# Power.net
KiCad netlist of a schematic drawn in Altium Designer
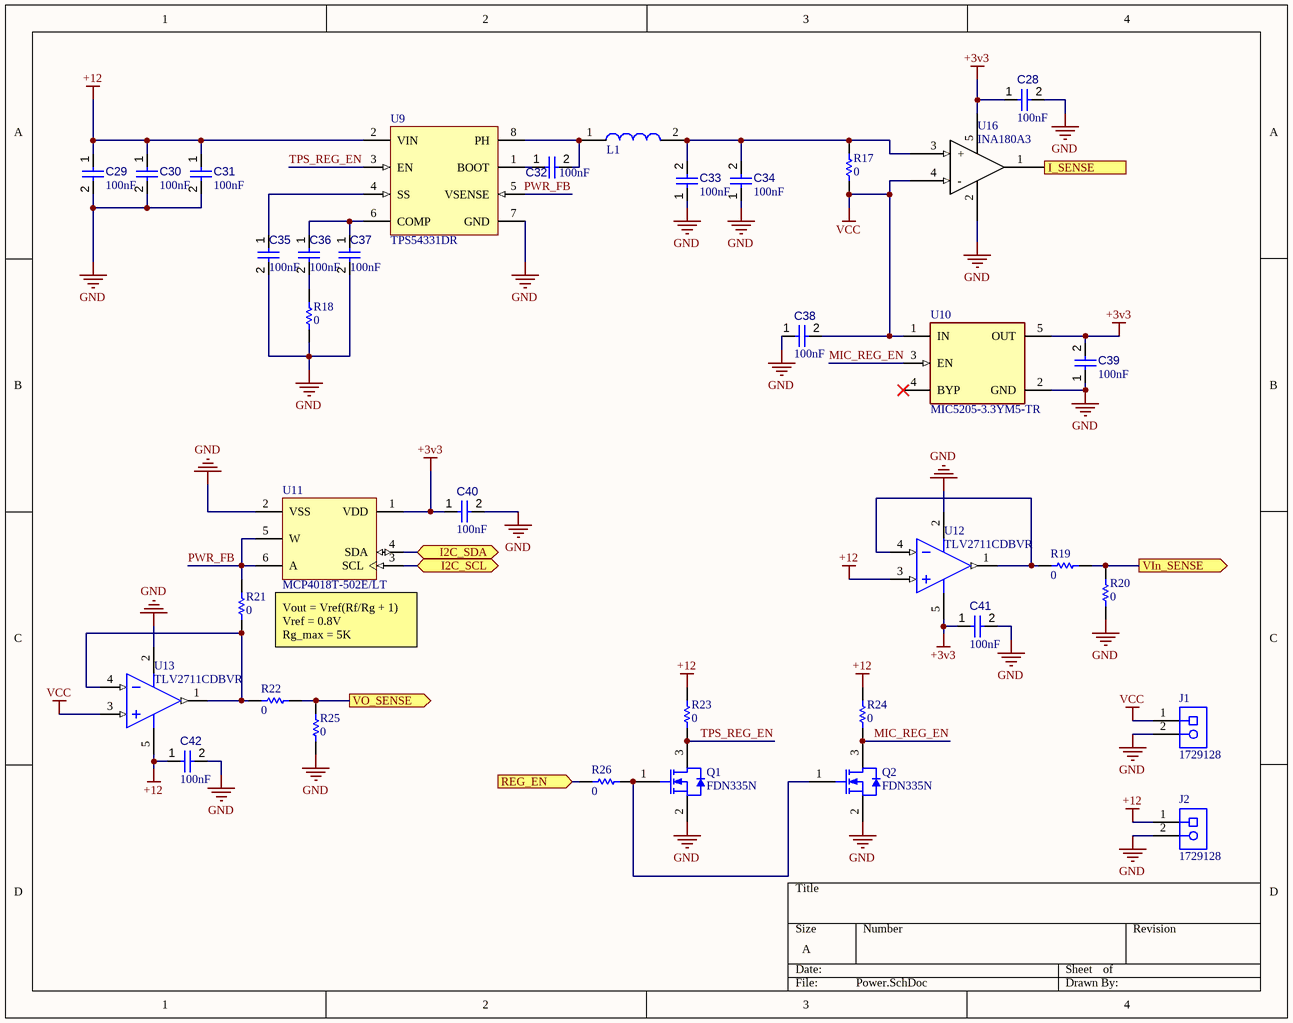
[diagram p0: Power.SchDoc]

(export (version "E")
  (design (tool "Eeschema 10.0.6"))
  (components
    (comp (ref "C28")
      (value "100nF")
      (footprint "CAPC2013X95X50ML10T25")
      (description "Chip Capacitor, 100 nF, +/- 10%, 50 V, 0805 (2012 Metric)")
      (fields (field (name "TOLERANCE") "10%") (field (name "Comment") "Capacitor 100 nF +/-10% 50 V 0805"))
      (libsource (lib "Aditya Sehgal") (part "CAP-NP-2"))
    )
    (comp (ref "C29")
      (value "100nF")
      (footprint "CAPC2013X95X50ML10T25")
      (description "Chip Capacitor, 100 nF, +/- 10%, 50 V, 0805 (2012 Metric)")
      (fields (field (name "TOLERANCE") "10%") (field (name "Comment") "Capacitor 100 nF +/-10% 50 V 0805"))
      (libsource (lib "Aditya Sehgal") (part "CAP-NP-2"))
    )
    (comp (ref "C30")
      (value "100nF")
      (footprint "CAPC2013X95X50ML10T25")
      (description "Chip Capacitor, 100 nF, +/- 10%, 50 V, 0805 (2012 Metric)")
      (fields (field (name "TOLERANCE") "10%") (field (name "Comment") "Capacitor 100 nF +/-10% 50 V 0805"))
      (libsource (lib "Aditya Sehgal") (part "CAP-NP-2"))
    )
    (comp (ref "C31")
      (value "100nF")
      (footprint "CAPC2013X95X50ML10T25")
      (description "Chip Capacitor, 100 nF, +/- 10%, 50 V, 0805 (2012 Metric)")
      (fields (field (name "TOLERANCE") "10%") (field (name "Comment") "Capacitor 100 nF +/-10% 50 V 0805"))
      (libsource (lib "Aditya Sehgal") (part "CAP-NP-2"))
    )
    (comp (ref "C32")
      (value "100nF")
      (footprint "CAPC2013X95X50ML10T25")
      (description "Chip Capacitor, 100 nF, +/- 10%, 50 V, 0805 (2012 Metric)")
      (fields (field (name "TOLERANCE") "10%") (field (name "Comment") "Capacitor 100 nF +/-10% 50 V 0805"))
      (libsource (lib "Aditya Sehgal") (part "CAP-NP-2"))
    )
    (comp (ref "C33")
      (value "100nF")
      (footprint "CAPC2013X95X50ML10T25")
      (description "Chip Capacitor, 100 nF, +/- 10%, 50 V, 0805 (2012 Metric)")
      (fields (field (name "TOLERANCE") "10%") (field (name "Comment") "Capacitor 100 nF +/-10% 50 V 0805"))
      (libsource (lib "Aditya Sehgal") (part "CAP-NP-2"))
    )
    (comp (ref "C34")
      (value "100nF")
      (footprint "CAPC2013X95X50ML10T25")
      (description "Chip Capacitor, 100 nF, +/- 10%, 50 V, 0805 (2012 Metric)")
      (fields (field (name "TOLERANCE") "10%") (field (name "Comment") "Capacitor 100 nF +/-10% 50 V 0805"))
      (libsource (lib "Aditya Sehgal") (part "CAP-NP-2"))
    )
    (comp (ref "C35")
      (value "100nF")
      (footprint "CAPC2013X95X50ML10T25")
      (description "Chip Capacitor, 100 nF, +/- 10%, 50 V, 0805 (2012 Metric)")
      (fields (field (name "TOLERANCE") "10%") (field (name "Comment") "Capacitor 100 nF +/-10% 50 V 0805"))
      (libsource (lib "Aditya Sehgal") (part "CAP-NP-2"))
    )
    (comp (ref "C36")
      (value "100nF")
      (footprint "CAPC2013X95X50ML10T25")
      (description "Chip Capacitor, 100 nF, +/- 10%, 50 V, 0805 (2012 Metric)")
      (fields (field (name "TOLERANCE") "10%") (field (name "Comment") "Capacitor 100 nF +/-10% 50 V 0805"))
      (libsource (lib "Aditya Sehgal") (part "CAP-NP-2"))
    )
    (comp (ref "C37")
      (value "100nF")
      (footprint "CAPC2013X95X50ML10T25")
      (description "Chip Capacitor, 100 nF, +/- 10%, 50 V, 0805 (2012 Metric)")
      (fields (field (name "TOLERANCE") "10%") (field (name "Comment") "Capacitor 100 nF +/-10% 50 V 0805"))
      (libsource (lib "Aditya Sehgal") (part "CAP-NP-2"))
    )
    (comp (ref "C38")
      (value "100nF")
      (footprint "CAPC2013X95X50ML10T25")
      (description "Chip Capacitor, 100 nF, +/- 10%, 50 V, 0805 (2012 Metric)")
      (fields (field (name "TOLERANCE") "10%") (field (name "Comment") "Capacitor 100 nF +/-10% 50 V 0805"))
      (libsource (lib "Aditya Sehgal") (part "CAP-NP-2"))
    )
    (comp (ref "C39")
      (value "100nF")
      (footprint "CAPC2013X95X50ML10T25")
      (description "Chip Capacitor, 100 nF, +/- 10%, 50 V, 0805 (2012 Metric)")
      (fields (field (name "TOLERANCE") "10%") (field (name "Comment") "Capacitor 100 nF +/-10% 50 V 0805"))
      (libsource (lib "Aditya Sehgal") (part "CAP-NP-2"))
    )
    (comp (ref "C40")
      (value "100nF")
      (footprint "CAPC2013X95X50ML10T25")
      (description "Chip Capacitor, 100 nF, +/- 10%, 50 V, 0805 (2012 Metric)")
      (fields (field (name "TOLERANCE") "10%") (field (name "Comment") "Capacitor 100 nF +/-10% 50 V 0805"))
      (libsource (lib "Aditya Sehgal") (part "CAP-NP-2"))
    )
    (comp (ref "C41")
      (value "100nF")
      (footprint "CAPC2013X95X50ML10T25")
      (description "Chip Capacitor, 100 nF, +/- 10%, 50 V, 0805 (2012 Metric)")
      (fields (field (name "TOLERANCE") "10%") (field (name "Comment") "Capacitor 100 nF +/-10% 50 V 0805"))
      (libsource (lib "Aditya Sehgal") (part "CAP-NP-2"))
    )
    (comp (ref "C42")
      (value "100nF")
      (footprint "CAPC2013X95X50ML10T25")
      (description "Chip Capacitor, 100 nF, +/- 10%, 50 V, 0805 (2012 Metric)")
      (fields (field (name "TOLERANCE") "10%") (field (name "Comment") "Capacitor 100 nF +/-10% 50 V 0805"))
      (libsource (lib "Aditya Sehgal") (part "CAP-NP-2"))
    )
    (comp (ref "J1")
      (value "1729128")
      (footprint "PHOE-1729128-2_V")
      (description "PCB Terminal Block, 13.5 A, 400 V, 2-Pin THD, RoHS, Bulk")
      (fields (field (name "MANUFACTURER") "Phoenix Contact"))
      (libsource (lib "Altium Content Vault") (part "CN-2P-F-R2"))
    )
    (comp (ref "J2")
      (value "1729128")
      (footprint "PHOE-1729128-2_V")
      (description "PCB Terminal Block, 13.5 A, 400 V, 2-Pin THD, RoHS, Bulk")
      (fields (field (name "MANUFACTURER") "Phoenix Contact"))
      (libsource (lib "Altium Content Vault") (part "CN-2P-F-R2"))
    )
    (comp (ref "L1")
      (value "LQH5BPN4R7NT0L")
      (footprint "LQH5BPN4R7NT0L-Footprint-1")
      (description "4.7uH 2A 58mOhm 5x5mm inductor Murata")
      (libsource (lib "Aditya Sehgal") (part "LQH5BPN4R7NT0L"))
    )
    (comp (ref "Q1")
      (value "FDN335N")
      (footprint "FAIR-SSOT3L-3_V")
      (fields (field (name "MANUFACTURER") "FairchildSemiconductor"))
      (libsource (lib "Altium Content Vault") (part "NEMOS-GSD-3"))
    )
    (comp (ref "Q2")
      (value "FDN335N")
      (footprint "FAIR-SSOT3L-3_V")
      (fields (field (name "MANUFACTURER") "FairchildSemiconductor"))
      (libsource (lib "Altium Content Vault") (part "NEMOS-GSD-3"))
    )
    (comp (ref "R17")
      (value "0")
      (footprint "RESC3216X60X45ML15T20")
      (description "Chip Resistor, 0 Ohm, +/- 5%, 0.25 W, -55 to 155 degC, 1206 (3216 Metric)")
      (fields (field (name "POWER") "250mW") (field (name "TOLERANCE") "5%"))
      (libsource (lib "Aditya Sehgal") (part "RES-2"))
    )
    (comp (ref "R18")
      (value "0")
      (footprint "RESC2013X50X35ML15T15")
      (description "Chip Resistor, 0 Ohm, +/- 1%, 125 mW, -55 to 155 degC, 0805 (2012 Metric)")
      (fields (field (name "TOLERANCE") "1%") (field (name "POWER") "125mW"))
      (libsource (lib "Aditya Sehgal") (part "RES-2"))
    )
    (comp (ref "R19")
      (value "0")
      (footprint "RESC2013X50X35ML15T15")
      (description "Chip Resistor, 0 Ohm, +/- 1%, 125 mW, -55 to 155 degC, 0805 (2012 Metric)")
      (fields (field (name "TOLERANCE") "1%") (field (name "POWER") "125mW"))
      (libsource (lib "Aditya Sehgal") (part "RES-2"))
    )
    (comp (ref "R20")
      (value "0")
      (footprint "RESC2013X50X35ML15T15")
      (description "Chip Resistor, 0 Ohm, +/- 1%, 125 mW, -55 to 155 degC, 0805 (2012 Metric)")
      (fields (field (name "TOLERANCE") "1%") (field (name "POWER") "125mW"))
      (libsource (lib "Aditya Sehgal") (part "RES-2"))
    )
    (comp (ref "R21")
      (value "0")
      (footprint "RESC2013X50X35ML15T15")
      (description "Chip Resistor, 0 Ohm, +/- 1%, 125 mW, -55 to 155 degC, 0805 (2012 Metric)")
      (fields (field (name "TOLERANCE") "1%") (field (name "POWER") "125mW"))
      (libsource (lib "Aditya Sehgal") (part "RES-2"))
    )
    (comp (ref "R22")
      (value "0")
      (footprint "RESC2013X50X35ML15T15")
      (description "Chip Resistor, 0 Ohm, +/- 1%, 125 mW, -55 to 155 degC, 0805 (2012 Metric)")
      (fields (field (name "TOLERANCE") "1%") (field (name "POWER") "125mW"))
      (libsource (lib "Aditya Sehgal") (part "RES-2"))
    )
    (comp (ref "R23")
      (value "0")
      (footprint "RESC2013X50X35ML15T15")
      (description "Chip Resistor, 0 Ohm, +/- 1%, 125 mW, -55 to 155 degC, 0805 (2012 Metric)")
      (fields (field (name "TOLERANCE") "1%") (field (name "POWER") "125mW"))
      (libsource (lib "Aditya Sehgal") (part "RES-2"))
    )
    (comp (ref "R24")
      (value "0")
      (footprint "RESC2013X50X35ML15T15")
      (description "Chip Resistor, 0 Ohm, +/- 1%, 125 mW, -55 to 155 degC, 0805 (2012 Metric)")
      (fields (field (name "TOLERANCE") "1%") (field (name "POWER") "125mW"))
      (libsource (lib "Aditya Sehgal") (part "RES-2"))
    )
    (comp (ref "R25")
      (value "0")
      (footprint "RESC2013X50X35ML15T15")
      (description "Chip Resistor, 0 Ohm, +/- 1%, 125 mW, -55 to 155 degC, 0805 (2012 Metric)")
      (fields (field (name "TOLERANCE") "1%") (field (name "POWER") "125mW"))
      (libsource (lib "Aditya Sehgal") (part "RES-2"))
    )
    (comp (ref "R26")
      (value "0")
      (footprint "RESC2013X50X35ML15T15")
      (description "Chip Resistor, 0 Ohm, +/- 1%, 125 mW, -55 to 155 degC, 0805 (2012 Metric)")
      (fields (field (name "TOLERANCE") "1%") (field (name "POWER") "125mW"))
      (libsource (lib "Aditya Sehgal") (part "RES-2"))
    )
    (comp (ref "U9")
      (value "TPS54331DR")
      (footprint "D0008A_L")
      (fields (field (name "MANUFACTURER") "Texas Instruments"))
      (libsource (lib "Altium Content Vault") (part "TI-TPS54331D8"))
    )
    (comp (ref "U10")
      (value "MIC5205-3.3YM5-TR")
      (footprint "FP-M5-IPC_C")
      (description "IC REG LINEAR 3.3V 150MA SOT23-5")
      (fields
        (field (name "MANUFACTURER") "Microchip")
        (field (name "OCTOPART") "https://octopart.com/mic5205-3.3ym5-tr-microchip-66802130")
      )
      (libsource (lib "Altium Content Vault") (part "b2bb7f462d557aec50a251fc6568b2e"))
    )
    (comp (ref "U11")
      (value "MCP4018T-502E/LT")
      (footprint "SC70-LT6_L")
      (description "7-Bit Single I2C Digital POT with Volatile Memory, 6-pin SC70, Extended Temperature, Tape and Reel")
      (libsource (lib "Altium Content Vault") (part "IN-DPOT-MCP4018-6"))
    )
    (comp (ref "U12")
      (value "TLV2711CDBVR")
      (footprint "DBV0005A_M")
      (fields (field (name "MANUFACTURER") "Texas Instruments"))
      (libsource (lib "Altium Content Vault") (part "TI-TLV27X1DBV5"))
    )
    (comp (ref "U13")
      (value "TLV2711CDBVR")
      (footprint "DBV0005A_M")
      (fields (field (name "MANUFACTURER") "Texas Instruments"))
      (libsource (lib "Altium Content Vault") (part "TI-TLV27X1DBV5"))
    )
    (comp (ref "U16")
      (value "INA180A3")
      (footprint "SOT95P245X110-5N")
      (description "Current Sense Amplifier 100V/V")
      (libsource (lib "Aditya Sehgal") (part "INA180A3"))
    )
  )
  (nets
    (net (code "1") (name "+3v3") (class "Default")
      (node (ref "C28") (pin "1") (pinfunction "1_1") (pintype "passive"))
      (node (ref "C39") (pin "2") (pinfunction "2_2") (pintype "passive"))
      (node (ref "C40") (pin "1") (pinfunction "1_1") (pintype "passive"))
      (node (ref "C41") (pin "1") (pinfunction "1_1") (pintype "passive"))
      (node (ref "U10") (pin "5") (pinfunction "OUT_5") (pintype "power_in"))
      (node (ref "U11") (pin "1") (pinfunction "VDD_1") (pintype "power_in"))
      (node (ref "U12") (pin "5") (pinfunction "VDD-/GND_5") (pintype "power_in"))
      (node (ref "U16") (pin "5") (pinfunction "Vcc_5") (pintype "passive"))
    )
    (net (code "2") (name "+12") (class "Default")
      (node (ref "C29") (pin "1") (pinfunction "1_1") (pintype "passive"))
      (node (ref "C30") (pin "1") (pinfunction "1_1") (pintype "passive"))
      (node (ref "C31") (pin "1") (pinfunction "1_1") (pintype "passive"))
      (node (ref "C42") (pin "1") (pinfunction "1_1") (pintype "passive"))
      (node (ref "J2") (pin "1") (pinfunction "1_1") (pintype "passive"))
      (node (ref "R23") (pin "2") (pinfunction "2_2") (pintype "passive"))
      (node (ref "R24") (pin "2") (pinfunction "2_2") (pintype "passive"))
      (node (ref "U12") (pin "3") (pinfunction "IN+_3") (pintype "input"))
      (node (ref "U13") (pin "5") (pinfunction "VDD-/GND_5") (pintype "power_in"))
      (node (ref "U9") (pin "2") (pinfunction "VIN_2") (pintype "power_in"))
    )
    (net (code "3") (name "/I2C_SCL") (class "Default")
      (node (ref "U11") (pin "3") (pinfunction "SCL_3") (pintype "input"))
    )
    (net (code "4") (name "/I2C_SDA") (class "Default")
      (node (ref "U11") (pin "4") (pinfunction "SDA_4") (pintype "bidirectional"))
    )
    (net (code "5") (name "/I_SENSE") (class "Default")
      (node (ref "U16") (pin "1") (pinfunction "out_1") (pintype "passive"))
    )
    (net (code "6") (name "/MIC_REG_EN") (class "Default")
      (node (ref "Q2") (pin "3") (pinfunction "D_3") (pintype "passive"))
      (node (ref "R24") (pin "1") (pinfunction "1_1") (pintype "passive"))
      (node (ref "U10") (pin "3") (pinfunction "EN_3") (pintype "input"))
    )
    (net (code "7") (name "/PWR_FB") (class "Default")
      (node (ref "R21") (pin "2") (pinfunction "2_2") (pintype "passive"))
      (node (ref "U11") (pin "5") (pinfunction "W_5") (pintype "passive"))
      (node (ref "U11") (pin "6") (pinfunction "A_6") (pintype "passive"))
      (node (ref "U9") (pin "5") (pinfunction "VSENSE_5") (pintype "input"))
    )
    (net (code "8") (name "/REG_EN") (class "Default")
      (node (ref "R26") (pin "1") (pinfunction "1_1") (pintype "passive"))
    )
    (net (code "9") (name "/TPS_REG_EN") (class "Default")
      (node (ref "Q1") (pin "3") (pinfunction "D_3") (pintype "passive"))
      (node (ref "R23") (pin "1") (pinfunction "1_1") (pintype "passive"))
      (node (ref "U9") (pin "3") (pinfunction "EN_3") (pintype "input"))
    )
    (net (code "10") (name "/VIn_SENSE") (class "Default")
      (node (ref "R19") (pin "2") (pinfunction "2_2") (pintype "passive"))
      (node (ref "R20") (pin "2") (pinfunction "2_2") (pintype "passive"))
    )
    (net (code "11") (name "/VO_SENSE") (class "Default")
      (node (ref "R22") (pin "2") (pinfunction "2_2") (pintype "passive"))
      (node (ref "R25") (pin "2") (pinfunction "2_2") (pintype "passive"))
    )
    (net (code "12") (name "GND") (class "Default")
      (node (ref "C28") (pin "2") (pinfunction "2_2") (pintype "passive"))
      (node (ref "C29") (pin "2") (pinfunction "2_2") (pintype "passive"))
      (node (ref "C30") (pin "2") (pinfunction "2_2") (pintype "passive"))
      (node (ref "C31") (pin "2") (pinfunction "2_2") (pintype "passive"))
      (node (ref "C33") (pin "1") (pinfunction "1_1") (pintype "passive"))
      (node (ref "C34") (pin "1") (pinfunction "1_1") (pintype "passive"))
      (node (ref "C35") (pin "2") (pinfunction "2_2") (pintype "passive"))
      (node (ref "C37") (pin "2") (pinfunction "2_2") (pintype "passive"))
      (node (ref "C38") (pin "1") (pinfunction "1_1") (pintype "passive"))
      (node (ref "C39") (pin "1") (pinfunction "1_1") (pintype "passive"))
      (node (ref "C40") (pin "2") (pinfunction "2_2") (pintype "passive"))
      (node (ref "C41") (pin "2") (pinfunction "2_2") (pintype "passive"))
      (node (ref "C42") (pin "2") (pinfunction "2_2") (pintype "passive"))
      (node (ref "J1") (pin "2") (pinfunction "2_2") (pintype "passive"))
      (node (ref "J2") (pin "2") (pinfunction "2_2") (pintype "passive"))
      (node (ref "Q1") (pin "2") (pinfunction "S_2") (pintype "passive"))
      (node (ref "Q2") (pin "2") (pinfunction "S_2") (pintype "passive"))
      (node (ref "R18") (pin "2") (pinfunction "2_2") (pintype "passive"))
      (node (ref "R20") (pin "1") (pinfunction "1_1") (pintype "passive"))
      (node (ref "R25") (pin "1") (pinfunction "1_1") (pintype "passive"))
      (node (ref "U10") (pin "2") (pinfunction "GND_2") (pintype "power_in"))
      (node (ref "U11") (pin "2") (pinfunction "VSS_2") (pintype "power_in"))
      (node (ref "U12") (pin "2") (pinfunction "VDD+_2") (pintype "power_in"))
      (node (ref "U13") (pin "2") (pinfunction "VDD+_2") (pintype "power_in"))
      (node (ref "U16") (pin "2") (pinfunction "GND_2") (pintype "power_in"))
      (node (ref "U9") (pin "7") (pinfunction "GND_7") (pintype "power_in"))
    )
    (net (code "13") (name "Net-(C36-Pad2)") (class "Default")
      (node (ref "C36") (pin "2") (pinfunction "2_2") (pintype "passive"))
      (node (ref "R18") (pin "1") (pinfunction "1_1") (pintype "passive"))
    )
    (net (code "14") (name "Net-(L1-7)") (class "Default")
      (node (ref "C32") (pin "2") (pinfunction "2_2") (pintype "passive"))
      (node (ref "L1") (pin "1") (pinfunction "7_1") (pintype "passive"))
      (node (ref "U9") (pin "8") (pinfunction "PH_8") (pintype "power_in"))
    )
    (net (code "15") (name "Net-(L1-8)") (class "Default")
      (node (ref "C33") (pin "2") (pinfunction "2_2") (pintype "passive"))
      (node (ref "C34") (pin "2") (pinfunction "2_2") (pintype "passive"))
      (node (ref "L1") (pin "2") (pinfunction "8_2") (pintype "passive"))
      (node (ref "R17") (pin "2") (pinfunction "2_2") (pintype "passive"))
      (node (ref "U16") (pin "3") (pinfunction "+_3") (pintype "input"))
    )
    (net (code "16") (name "Net-(Q1-G)") (class "Default")
      (node (ref "Q1") (pin "1") (pinfunction "G_1") (pintype "passive"))
      (node (ref "Q2") (pin "1") (pinfunction "G_1") (pintype "passive"))
      (node (ref "R26") (pin "2") (pinfunction "2_2") (pintype "passive"))
    )
    (net (code "17") (name "Net-(U9-BOOT)") (class "Default")
      (node (ref "C32") (pin "1") (pinfunction "1_1") (pintype "passive"))
      (node (ref "U9") (pin "1") (pinfunction "BOOT_1") (pintype "passive"))
    )
    (net (code "18") (name "Net-(U9-COMP)") (class "Default")
      (node (ref "C36") (pin "1") (pinfunction "1_1") (pintype "passive"))
      (node (ref "C37") (pin "1") (pinfunction "1_1") (pintype "passive"))
      (node (ref "U9") (pin "6") (pinfunction "COMP_6") (pintype "passive"))
    )
    (net (code "19") (name "Net-(U9-SS)") (class "Default")
      (node (ref "C35") (pin "1") (pinfunction "1_1") (pintype "passive"))
      (node (ref "U9") (pin "4") (pinfunction "SS_4") (pintype "input"))
    )
    (net (code "20") (name "Net-(U12-IN-)") (class "Default")
      (node (ref "R19") (pin "1") (pinfunction "1_1") (pintype "passive"))
      (node (ref "U12") (pin "1") (pinfunction "OUT_1") (pintype "output"))
      (node (ref "U12") (pin "4") (pinfunction "IN-_4") (pintype "input"))
    )
    (net (code "21") (name "Net-(U13-IN-)") (class "Default")
      (node (ref "R21") (pin "1") (pinfunction "1_1") (pintype "passive"))
      (node (ref "R22") (pin "1") (pinfunction "1_1") (pintype "passive"))
      (node (ref "U13") (pin "1") (pinfunction "OUT_1") (pintype "output"))
      (node (ref "U13") (pin "4") (pinfunction "IN-_4") (pintype "input"))
    )
    (net (code "22") (name "VCC") (class "Default")
      (node (ref "C38") (pin "2") (pinfunction "2_2") (pintype "passive"))
      (node (ref "J1") (pin "1") (pinfunction "1_1") (pintype "passive"))
      (node (ref "R17") (pin "1") (pinfunction "1_1") (pintype "passive"))
      (node (ref "U10") (pin "1") (pinfunction "IN_1") (pintype "power_in"))
      (node (ref "U13") (pin "3") (pinfunction "IN+_3") (pintype "input"))
      (node (ref "U16") (pin "4") (pinfunction "-_4") (pintype "input"))
    )
    (net (code "23") (name "unconnected-(U10-BYP-Pad4)") (class "Default")
      (node (ref "U10") (pin "4") (pinfunction "BYP_4") (pintype "passive+no_connect"))
    )
  )
)
